# Controller_Sheet.net
KiCad netlist of a schematic drawn in Altium Designer
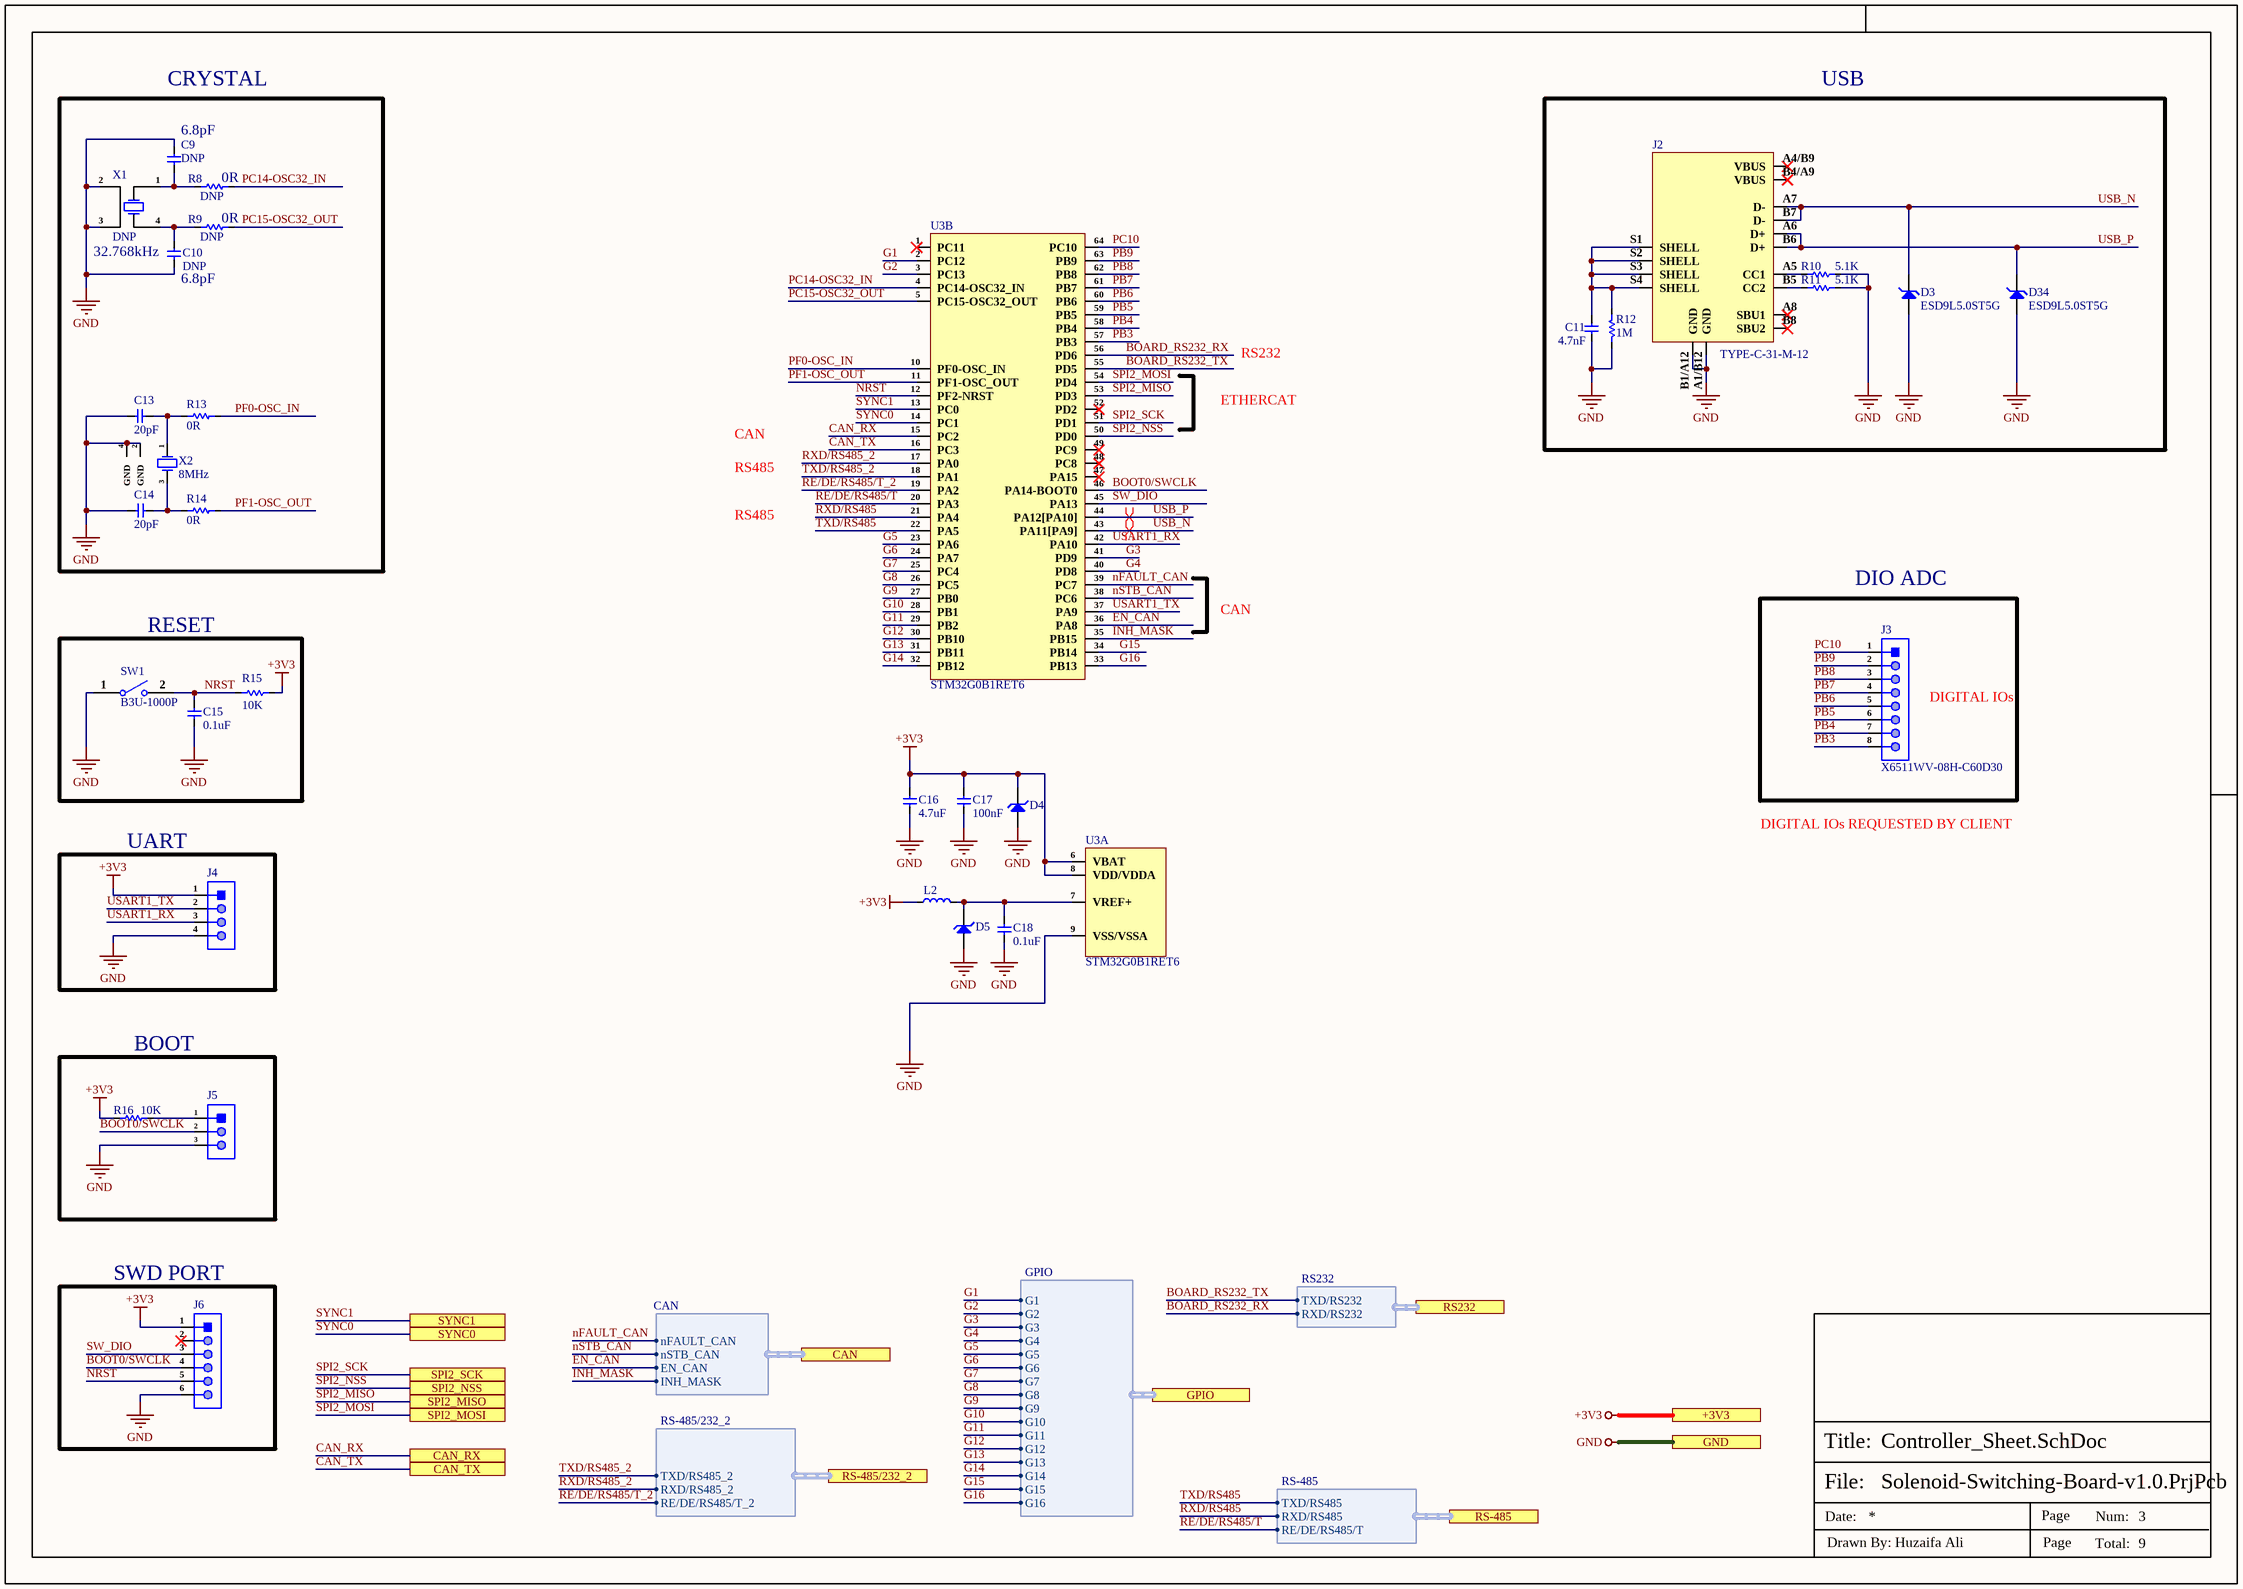
[diagram p0: Controller_Sheet.SchDoc]

(export (version "E")
  (design (tool "Eeschema 10.0.6"))
  (components
    (comp (ref "C9")
      (value "DNP")
      (footprint "Cap-0402")
      (description "CAP CER 6.8PF 50V C0G/NPO 0402")
      (fields
        (field (name "MANUFACTURER") "Yageo")
        (field (name "MANUFACTURER PART NUMBER") "CC0402CRNPO9BN6R8")
      )
      (libsource (lib "eSpark Libraries") (part "CC0402CRNPO9BN6R8"))
    )
    (comp (ref "C10")
      (value "DNP")
      (footprint "Cap-0402")
      (description "CAP CER 6.8PF 50V C0G/NPO 0402")
      (fields
        (field (name "MANUFACTURER") "Yageo")
        (field (name "MANUFACTURER PART NUMBER") "CC0402CRNPO9BN6R8")
      )
      (libsource (lib "eSpark Libraries") (part "CC0402CRNPO9BN6R8"))
    )
    (comp (ref "C11")
      (value "4.7nF")
      (footprint "Cap-0603")
      (description "CAP CER 4700PF 50V C0G/NPO 0603")
      (fields
        (field (name "MANUFACTURER") "Yageo")
        (field (name "MANUFACTURER PART NUMBER") "CC0603JRNPO9BN472")
      )
      (libsource (lib "eSpark_centralized_Library(2022)") (part "CC0603JRNPO9BN472"))
    )
    (comp (ref "C13")
      (value "20pF")
      (footprint "Cap-0402")
      (description "CAP CER 20PF 50V C0G/NPO 0402")
      (fields (field (name "LCSC PART NUMBER") "C107000") (field (name "MANUFACTURER") "Yageo"))
      (libsource (lib "eSpark Libraries") (part "CC0402JRNPO9BN200"))
    )
    (comp (ref "C14")
      (value "20pF")
      (footprint "Cap-0402")
      (description "CAP CER 20PF 50V C0G/NPO 0402")
      (fields (field (name "LCSC PART NUMBER") "C107000") (field (name "MANUFACTURER") "Yageo"))
      (libsource (lib "eSpark Libraries") (part "CC0402JRNPO9BN200"))
    )
    (comp (ref "C15")
      (value "0.1uF")
      (footprint "Cap-0402")
      (description "CAP CER 0.1UF 16V X7R 0402")
      (fields
        (field (name "MANUFACTURER") "Yageo")
        (field (name "MANUFACTURER PART NUMBER") "CC0402JRX7R7BB104")
      )
      (libsource (lib "eSpark Libraries") (part "CC0402JRX7R7BB104"))
    )
    (comp (ref "C16")
      (value "4.7uF")
      (footprint "Cap-0402")
      (description "CAP CER 4.7UF 10V X5R 0402")
      (fields
        (field (name "MANUFACTURER") "Yageo")
        (field (name "MANUFACTURER PART NUMBER") "CC0402KRX5R6BB475")
      )
      (libsource (lib "eSpark Libraries") (part "CC0402KRX5R6BB475"))
    )
    (comp (ref "C17")
      (value "100nF")
      (footprint "cap-0402")
      (description "CAP CER 0.1UF 50V X7R 0402")
      (fields
        (field (name "MANUFACTURER") "TDK")
        (field (name "MANUFACTURER PART NUMBER") "C1005X7R1H104KT000F")
      )
      (libsource (lib "eSpark Libraries") (part "C1005X7R1H104KT000F"))
    )
    (comp (ref "C18")
      (value "0.1uF")
      (footprint "Cap-0402")
      (description "CAP CER 0.1UF 16V X7R 0402")
      (fields
        (field (name "MANUFACTURER") "Yageo")
        (field (name "MANUFACTURER PART NUMBER") "CC0402JRX7R7BB104")
      )
      (libsource (lib "eSpark Libraries") (part "CC0402JRX7R7BB104"))
    )
    (comp (ref "D3")
      (value "ESD9L5.0ST5G")
      (footprint "SOD-923.")
      (description "TVS DIODE 5V 9.8V SOD923")
      (fields (field (name "MANUFACTURER") "ON Semiconductor") (field (name "LCSC PART NUMBER") "C82326"))
      (libsource (lib "eSpark Libraries") (part "ESD9L5.0ST5G"))
    )
    (comp (ref "D4")
      (value "AZ3003-01G")
      (footprint "SOD-123")
      (description "TVS SURGE PROTECTOR 1-CH 3.3V")
      (fields (field (name "MANUFACTURER") "Amazing"))
      (libsource (lib "eSpark Libraries") (part "AZ3003-01G"))
    )
    (comp (ref "D5")
      (value "AZ3003-01G")
      (footprint "SOD-123")
      (description "TVS SURGE PROTECTOR 1-CH 3.3V")
      (fields (field (name "MANUFACTURER") "Amazing"))
      (libsource (lib "eSpark Libraries") (part "AZ3003-01G"))
    )
    (comp (ref "D34")
      (value "ESD9L5.0ST5G")
      (footprint "SOD-923.")
      (description "TVS DIODE 5V 9.8V SOD923")
      (fields (field (name "MANUFACTURER") "ON Semiconductor") (field (name "LCSC PART NUMBER") "C82326"))
      (libsource (lib "eSpark Libraries") (part "ESD9L5.0ST5G"))
    )
    (comp (ref "J2")
      (value "TYPE-C-31-M-12")
      (footprint "TYPE-C-31-M-12_")
      (description "5A 1 16P Female Type-C SMD USB Connectors ROHS")
      (fields
        (field (name "MANUFACTURER") "Korean Hroparts Elec")
        (field (name "LCSC PART NUMBER") "C165948")
      )
      (libsource (lib "eSpark Libraries") (part "TYPE-C-31-M-12"))
    )
    (comp (ref "J3")
      (value "X6511WV-08H-C60D30")
      (footprint "HDR 1x8 TH male")
      (fields (field (name "MANUFACTURER") "XKB") (field (name "LCSC PART NUMBER") "C706880"))
      (libsource (lib "eSpark Libraries") (part "X6511WV-08H-C60D30"))
    )
    (comp (ref "J4")
      (value "X6511WV-04H-C60D30")
      (footprint "HDR1X4_")
      (fields (field (name "MANUFACTURER") "XKB") (field (name "LCSC PART NUMBER") "C706876"))
      (libsource (lib "eSpark Libraries") (part "X6511WV-04H-C60D30"))
    )
    (comp (ref "J5")
      (value "68000-103HLF")
      (footprint "HDR1X3_")
      (description "CONN HEADER VERT 3POS 2.54MM")
      (fields (field (name "LCSC PART NUMBER") "C168677"))
      (libsource (lib "eSpark Libraries") (part "68000-103HLF"))
    )
    (comp (ref "J6")
      (value "X6511WV-06H-C60D30")
      (footprint "HDR1X6_")
      (fields (field (name "MANUFACTURER") "XKB") (field (name "LCSC PART NUMBER") "C706878"))
      (libsource (lib "eSpark Libraries") (part "X6511WV-06H-C60D30"))
    )
    (comp (ref "L2")
      (value "BLM15AG601SN1D")
      (footprint "IND-0402")
      (description "FERRITE BEAD 600 OHM 0402 1LN")
      (fields (field (name "MANUFACTURER") "Murata") (field (name "TOLERANCE") "25%"))
      (libsource (lib "eSpark Libraries") (part "BLM15AG601SN1D"))
    )
    (comp (ref "R8")
      (value "DNP")
      (footprint "Res-0603")
      (description "RES 0 OHM JUMPER 1/10W 0603")
      (fields
        (field (name "MANUFACTURER") "Yageo")
        (field (name "MANUFACTURER PART NUMBER") "RC0603JR-070RL")
      )
      (libsource (lib "eSpark Libraries") (part "RC0603JR-070RL"))
    )
    (comp (ref "R9")
      (value "DNP")
      (footprint "Res-0603")
      (description "RES 0 OHM JUMPER 1/10W 0603")
      (fields
        (field (name "MANUFACTURER") "Yageo")
        (field (name "MANUFACTURER PART NUMBER") "RC0603JR-070RL")
      )
      (libsource (lib "eSpark Libraries") (part "RC0603JR-070RL"))
    )
    (comp (ref "R10")
      (value "5.1K")
      (footprint "Res-0402")
      (description "RES 5.1K OHM 1% 1/16W 0402")
      (fields
        (field (name "MANUFACTURER") "Yageo")
        (field (name "MANUFACTURER PART NUMBER") "RC0402FR-075K1L")
      )
      (libsource (lib "eSpark Libraries") (part "RC0402FR-075K1L"))
    )
    (comp (ref "R11")
      (value "5.1K")
      (footprint "Res-0402")
      (description "RES 5.1K OHM 1% 1/16W 0402")
      (fields
        (field (name "MANUFACTURER") "Yageo")
        (field (name "MANUFACTURER PART NUMBER") "RC0402FR-075K1L")
      )
      (libsource (lib "eSpark Libraries") (part "RC0402FR-075K1L"))
    )
    (comp (ref "R12")
      (value "1M")
      (footprint "Res-0402")
      (description "RES SMD 1M OHM 5% 1/16W 0402")
      (fields
        (field (name "MANUFACTURER") "Yageo")
        (field (name "MANUFACTURER PART NUMBER") "AF0402JR-071ML")
      )
      (libsource (lib "eSpark_centralized_Library(2022)") (part "AF0402JR-071ML"))
    )
    (comp (ref "R13")
      (value "0R")
      (footprint "Res-0603")
      (description "RES 0 OHM JUMPER 1/10W 0603")
      (fields
        (field (name "MANUFACTURER") "Yageo")
        (field (name "MANUFACTURER PART NUMBER") "RC0603JR-070RL")
      )
      (libsource (lib "eSpark Libraries") (part "RC0603JR-070RL"))
    )
    (comp (ref "R14")
      (value "0R")
      (footprint "Res-0603")
      (description "RES 0 OHM JUMPER 1/10W 0603")
      (fields
        (field (name "MANUFACTURER") "Yageo")
        (field (name "MANUFACTURER PART NUMBER") "RC0603JR-070RL")
      )
      (libsource (lib "eSpark Libraries") (part "RC0603JR-070RL"))
    )
    (comp (ref "R15")
      (value "10K")
      (footprint "Res-0402")
      (description "RES 10K OHM 1% 1/16W 0402")
      (fields
        (field (name "MANUFACTURER") "Yageo")
        (field (name "MANUFACTURER PART NUMBER") "RC0402FR-0710KL")
      )
      (libsource (lib "eSpark Libraries") (part "RC0402FR-0710KL"))
    )
    (comp (ref "R16")
      (value "10K")
      (footprint "Res-0402")
      (description "RES 10K OHM 1% 1/16W 0402")
      (fields
        (field (name "MANUFACTURER") "Yageo")
        (field (name "MANUFACTURER PART NUMBER") "RC0402FR-0710KL")
      )
      (libsource (lib "eSpark Libraries") (part "RC0402FR-0710KL"))
    )
    (comp (ref "SW1")
      (value "B3U-1000P")
      (footprint "B3U-1000P")
      (description "SWITCH TACTILE SPST-NO 0.05A 12V")
      (fields (field (name "MANUFACTURER") "Omron") (field (name "LCSC PART NUMBER") "C231329"))
      (libsource (lib "eSpark Libraries") (part "B3U-1000P"))
    )
    (comp (ref "U3")
      (value "STM32G0B1RET6")
      (footprint "LQFP-64(10x10)")
      (description "IC MCU 32BIT 512KB FLASH 64LQFP")
      (fields (field (name "MANUFACTURER") "STMicroelectronics") (field (name "LCSC PART NUMBER") "C2829307"))
      (libsource (lib "eSpark Libraries") (part "STM32G0B1RET6"))
    )
    (comp (ref "X1")
      (value "DNP")
      (footprint "MC-306")
      (description "32.768kHz 12.5pF ±20ppm MC-306 Crystals ROHS")
      (fields
        (field (name "MANUFACTURER") "Seiko Epson")
        (field (name "MANUFACTURER PART NUMBER") "MC-306 32.7680K-A0:ROHS")
      )
      (libsource (lib "eSpark Libraries") (part "MC-306 32.7680K-A0{colon}ROHS"))
    )
    (comp (ref "X2")
      (value "8MHz")
      (footprint "5TJ480000XYLBC_")
      (description "8MHz 18pF ±10ppm SMD5032-4P Crystals ROHS")
      (fields (field (name "MANUFACTURER") "JYJE") (field (name "MANUFACTURER PART NUMBER") "5TJ480000XYLBC"))
      (libsource (lib "eSpark Libraries") (part "5TJ480000XYLBC"))
    )
  )
  (nets
    (net (code "6") (name "+3V3") (class "Default")
      (node (ref "C16") (pin "2") (pinfunction "2_2") (pintype "passive"))
      (node (ref "C17") (pin "2") (pinfunction "2_2") (pintype "passive"))
      (node (ref "D4") (pin "2") (pinfunction "K_2") (pintype "passive"))
      (node (ref "J4") (pin "1") (pinfunction "1_1") (pintype "passive"))
      (node (ref "J6") (pin "1") (pinfunction "1_1") (pintype "passive"))
      (node (ref "L2") (pin "1") (pinfunction "1_1") (pintype "passive"))
      (node (ref "R15") (pin "2") (pinfunction "2_2") (pintype "passive"))
      (node (ref "R16") (pin "2") (pinfunction "2_2") (pintype "passive"))
      (node (ref "U3") (pin "6") (pinfunction "VBAT_6") (pintype "passive"))
      (node (ref "U3") (pin "8") (pinfunction "VDD/VDDA_8") (pintype "passive"))
    )
    (net (code "7") (name "/BOARD_RS232_RX") (class "Default")
      (node (ref "U3") (pin "56") (pinfunction "PD6_56") (pintype "passive"))
    )
    (net (code "8") (name "/BOARD_RS232_TX") (class "Default")
      (node (ref "U3") (pin "55") (pinfunction "PD5_55") (pintype "passive"))
    )
    (net (code "9") (name "/BOOT0{slash}SWCLK") (class "Default")
      (node (ref "J5") (pin "2") (pinfunction "2_2") (pintype "passive"))
      (node (ref "J6") (pin "4") (pinfunction "4_4") (pintype "passive"))
      (node (ref "U3") (pin "46") (pinfunction "PA14-BOOT0_46") (pintype "passive"))
    )
    (net (code "10") (name "/CAN_RX") (class "Default")
      (node (ref "U3") (pin "15") (pinfunction "PC2_15") (pintype "passive"))
    )
    (net (code "11") (name "/CAN_TX") (class "Default")
      (node (ref "U3") (pin "16") (pinfunction "PC3_16") (pintype "passive"))
    )
    (net (code "12") (name "/EN_CAN") (class "Default")
      (node (ref "U3") (pin "36") (pinfunction "PA8_36") (pintype "passive"))
    )
    (net (code "13") (name "/G1") (class "Default")
      (node (ref "U3") (pin "2") (pinfunction "PC12_2") (pintype "passive"))
    )
    (net (code "14") (name "/G2") (class "Default")
      (node (ref "U3") (pin "3") (pinfunction "PC13_3") (pintype "passive"))
    )
    (net (code "15") (name "/G3") (class "Default")
      (node (ref "U3") (pin "41") (pinfunction "PD9_41") (pintype "passive"))
    )
    (net (code "16") (name "/G4") (class "Default")
      (node (ref "U3") (pin "40") (pinfunction "PD8_40") (pintype "passive"))
    )
    (net (code "17") (name "/G5") (class "Default")
      (node (ref "U3") (pin "23") (pinfunction "PA6_23") (pintype "passive"))
    )
    (net (code "18") (name "/G6") (class "Default")
      (node (ref "U3") (pin "24") (pinfunction "PA7_24") (pintype "passive"))
    )
    (net (code "19") (name "/G7") (class "Default")
      (node (ref "U3") (pin "25") (pinfunction "PC4_25") (pintype "passive"))
    )
    (net (code "20") (name "/G8") (class "Default")
      (node (ref "U3") (pin "26") (pinfunction "PC5_26") (pintype "passive"))
    )
    (net (code "21") (name "/G9") (class "Default")
      (node (ref "U3") (pin "27") (pinfunction "PB0_27") (pintype "passive"))
    )
    (net (code "22") (name "/G10") (class "Default")
      (node (ref "U3") (pin "28") (pinfunction "PB1_28") (pintype "passive"))
    )
    (net (code "23") (name "/G11") (class "Default")
      (node (ref "U3") (pin "29") (pinfunction "PB2_29") (pintype "passive"))
    )
    (net (code "24") (name "/G12") (class "Default")
      (node (ref "U3") (pin "30") (pinfunction "PB10_30") (pintype "passive"))
    )
    (net (code "25") (name "/G13") (class "Default")
      (node (ref "U3") (pin "31") (pinfunction "PB11_31") (pintype "passive"))
    )
    (net (code "26") (name "/G14") (class "Default")
      (node (ref "U3") (pin "32") (pinfunction "PB12_32") (pintype "passive"))
    )
    (net (code "27") (name "/G15") (class "Default")
      (node (ref "U3") (pin "34") (pinfunction "PB14_34") (pintype "passive"))
    )
    (net (code "28") (name "/G16") (class "Default")
      (node (ref "U3") (pin "33") (pinfunction "PB13_33") (pintype "passive"))
    )
    (net (code "29") (name "/INH_MASK") (class "Default")
      (node (ref "U3") (pin "35") (pinfunction "PB15_35") (pintype "passive"))
    )
    (net (code "30") (name "/NRST") (class "Default")
      (node (ref "C15") (pin "2") (pinfunction "2_2") (pintype "passive"))
      (node (ref "J6") (pin "5") (pinfunction "5_5") (pintype "passive"))
      (node (ref "R15") (pin "1") (pinfunction "1_1") (pintype "passive"))
      (node (ref "SW1") (pin "2") (pinfunction "2_2") (pintype "passive"))
      (node (ref "U3") (pin "12") (pinfunction "PF2-NRST_12") (pintype "passive"))
    )
    (net (code "31") (name "/PB3") (class "Default")
      (node (ref "J3") (pin "8") (pinfunction "8_8") (pintype "passive"))
      (node (ref "U3") (pin "57") (pinfunction "PB3_57") (pintype "passive"))
    )
    (net (code "32") (name "/PB4") (class "Default")
      (node (ref "J3") (pin "7") (pinfunction "7_7") (pintype "passive"))
      (node (ref "U3") (pin "58") (pinfunction "PB4_58") (pintype "passive"))
    )
    (net (code "33") (name "/PB5") (class "Default")
      (node (ref "J3") (pin "6") (pinfunction "6_6") (pintype "passive"))
      (node (ref "U3") (pin "59") (pinfunction "PB5_59") (pintype "passive"))
    )
    (net (code "34") (name "/PB6") (class "Default")
      (node (ref "J3") (pin "5") (pinfunction "5_5") (pintype "passive"))
      (node (ref "U3") (pin "60") (pinfunction "PB6_60") (pintype "passive"))
    )
    (net (code "35") (name "/PB7") (class "Default")
      (node (ref "J3") (pin "4") (pinfunction "4_4") (pintype "passive"))
      (node (ref "U3") (pin "61") (pinfunction "PB7_61") (pintype "passive"))
    )
    (net (code "36") (name "/PB8") (class "Default")
      (node (ref "J3") (pin "3") (pinfunction "3_3") (pintype "passive"))
      (node (ref "U3") (pin "62") (pinfunction "PB8_62") (pintype "passive"))
    )
    (net (code "37") (name "/PB9") (class "Default")
      (node (ref "J3") (pin "2") (pinfunction "2_2") (pintype "passive"))
      (node (ref "U3") (pin "63") (pinfunction "PB9_63") (pintype "passive"))
    )
    (net (code "38") (name "/PC10") (class "Default")
      (node (ref "J3") (pin "1") (pinfunction "1_1") (pintype "passive"))
      (node (ref "U3") (pin "64") (pinfunction "PC10_64") (pintype "passive"))
    )
    (net (code "39") (name "/PC14-OSC32_IN") (class "Default")
      (node (ref "R8") (pin "2") (pinfunction "2_2") (pintype "passive"))
      (node (ref "U3") (pin "4") (pinfunction "PC14-OSC32_IN_4") (pintype "passive"))
    )
    (net (code "40") (name "/PC15-OSC32_OUT") (class "Default")
      (node (ref "R9") (pin "2") (pinfunction "2_2") (pintype "passive"))
      (node (ref "U3") (pin "5") (pinfunction "PC15-OSC32_OUT_5") (pintype "passive"))
    )
    (net (code "41") (name "/PF0-OSC_IN") (class "Default")
      (node (ref "R13") (pin "2") (pinfunction "2_2") (pintype "passive"))
      (node (ref "U3") (pin "10") (pinfunction "PF0-OSC_IN_10") (pintype "passive"))
    )
    (net (code "42") (name "/PF1-OSC_OUT") (class "Default")
      (node (ref "R14") (pin "2") (pinfunction "2_2") (pintype "passive"))
      (node (ref "U3") (pin "11") (pinfunction "PF1-OSC_OUT_11") (pintype "passive"))
    )
    (net (code "43") (name "/RE{slash}DE{slash}RS485{slash}T") (class "Default")
      (node (ref "U3") (pin "20") (pinfunction "PA3_20") (pintype "passive"))
    )
    (net (code "44") (name "/RE{slash}DE{slash}RS485{slash}T_2") (class "Default")
      (node (ref "U3") (pin "19") (pinfunction "PA2_19") (pintype "passive"))
    )
    (net (code "45") (name "/RXD{slash}RS485") (class "Default")
      (node (ref "U3") (pin "21") (pinfunction "PA4_21") (pintype "passive"))
    )
    (net (code "46") (name "/RXD{slash}RS485_2") (class "Default")
      (node (ref "U3") (pin "17") (pinfunction "PA0_17") (pintype "passive"))
    )
    (net (code "47") (name "/SPI2_MISO") (class "Default")
      (node (ref "U3") (pin "53") (pinfunction "PD3_53") (pintype "passive"))
    )
    (net (code "48") (name "/SPI2_MOSI") (class "Default")
      (node (ref "U3") (pin "54") (pinfunction "PD4_54") (pintype "passive"))
    )
    (net (code "49") (name "/SPI2_NSS") (class "Default")
      (node (ref "U3") (pin "50") (pinfunction "PD0_50") (pintype "passive"))
    )
    (net (code "50") (name "/SPI2_SCK") (class "Default")
      (node (ref "U3") (pin "51") (pinfunction "PD1_51") (pintype "passive"))
    )
    (net (code "51") (name "/SW_DIO") (class "Default")
      (node (ref "J6") (pin "3") (pinfunction "3_3") (pintype "passive"))
      (node (ref "U3") (pin "45") (pinfunction "PA13_45") (pintype "passive"))
    )
    (net (code "52") (name "/SYNC0") (class "Default")
      (node (ref "U3") (pin "14") (pinfunction "PC1_14") (pintype "passive"))
    )
    (net (code "53") (name "/SYNC1") (class "Default")
      (node (ref "U3") (pin "13") (pinfunction "PC0_13") (pintype "passive"))
    )
    (net (code "54") (name "/TXD{slash}RS485") (class "Default")
      (node (ref "U3") (pin "22") (pinfunction "PA5_22") (pintype "passive"))
    )
    (net (code "55") (name "/TXD{slash}RS485_2") (class "Default")
      (node (ref "U3") (pin "18") (pinfunction "PA1_18") (pintype "passive"))
    )
    (net (code "56") (name "/USART1_RX") (class "Default")
      (node (ref "J4") (pin "3") (pinfunction "3_3") (pintype "passive"))
      (node (ref "U3") (pin "42") (pinfunction "PA10_42") (pintype "passive"))
    )
    (net (code "57") (name "/USART1_TX") (class "Default")
      (node (ref "J4") (pin "2") (pinfunction "2_2") (pintype "passive"))
      (node (ref "U3") (pin "37") (pinfunction "PA9_37") (pintype "passive"))
    )
    (net (code "58") (name "/USB_N") (class "Default")
      (node (ref "D3") (pin "1") (pinfunction "K_1") (pintype "passive"))
      (node (ref "J2") (pin "A7") (pinfunction "D-_A7") (pintype "passive"))
      (node (ref "J2") (pin "B7") (pinfunction "D-_B7") (pintype "passive"))
      (node (ref "U3") (pin "43") (pinfunction "PA11[PA9]_43") (pintype "passive"))
    )
    (net (code "59") (name "/USB_P") (class "Default")
      (node (ref "D34") (pin "1") (pinfunction "K_1") (pintype "passive"))
      (node (ref "J2") (pin "A6") (pinfunction "D+_A6") (pintype "passive"))
      (node (ref "J2") (pin "B6") (pinfunction "D+_B6") (pintype "passive"))
      (node (ref "U3") (pin "44") (pinfunction "PA12[PA10]_44") (pintype "passive"))
    )
    (net (code "60") (name "/nFAULT_CAN") (class "Default")
      (node (ref "U3") (pin "39") (pinfunction "PC7_39") (pintype "passive"))
    )
    (net (code "61") (name "/nSTB_CAN") (class "Default")
      (node (ref "U3") (pin "38") (pinfunction "PC6_38") (pintype "passive"))
    )
    (net (code "67") (name "GND") (class "Default")
      (node (ref "C10") (pin "2") (pinfunction "2_2") (pintype "passive"))
      (node (ref "C11") (pin "1") (pinfunction "1_1") (pintype "passive"))
      (node (ref "C13") (pin "1") (pinfunction "1_1") (pintype "passive"))
      (node (ref "C14") (pin "2") (pinfunction "2_2") (pintype "passive"))
      (node (ref "C15") (pin "1") (pinfunction "1_1") (pintype "passive"))
      (node (ref "C16") (pin "1") (pinfunction "1_1") (pintype "passive"))
      (node (ref "C17") (pin "1") (pinfunction "1_1") (pintype "passive"))
      (node (ref "C18") (pin "1") (pinfunction "1_1") (pintype "passive"))
      (node (ref "C9") (pin "1") (pinfunction "1_1") (pintype "passive"))
      (node (ref "D3") (pin "2") (pinfunction "A_2") (pintype "passive"))
      (node (ref "D34") (pin "2") (pinfunction "A_2") (pintype "passive"))
      (node (ref "D4") (pin "1") (pinfunction "A_1") (pintype "passive"))
      (node (ref "D5") (pin "1") (pinfunction "A_1") (pintype "passive"))
      (node (ref "J2") (pin "A1/B12") (pinfunction "GND_A1/B12") (pintype "power_in"))
      (node (ref "J2") (pin "B1/A12") (pinfunction "GND_B1/A12") (pintype "power_in"))
      (node (ref "J4") (pin "4") (pinfunction "4_4") (pintype "passive"))
      (node (ref "J5") (pin "3") (pinfunction "3_3") (pintype "passive"))
      (node (ref "J6") (pin "6") (pinfunction "6_6") (pintype "passive"))
      (node (ref "R10") (pin "2") (pinfunction "2_2") (pintype "passive"))
      (node (ref "R11") (pin "2") (pinfunction "2_2") (pintype "passive"))
      (node (ref "R12") (pin "2") (pinfunction "2_2") (pintype "passive"))
      (node (ref "SW1") (pin "1") (pinfunction "1_1") (pintype "passive"))
      (node (ref "U3") (pin "9") (pinfunction "VSS/VSSA_9") (pintype "passive"))
      (node (ref "X1") (pin "2") (pinfunction "2_2") (pintype "passive"))
      (node (ref "X1") (pin "3") (pinfunction "3_3") (pintype "passive"))
      (node (ref "X2") (pin "2") (pinfunction "GND_2") (pintype "passive"))
      (node (ref "X2") (pin "4") (pinfunction "GND_4") (pintype "passive"))
    )
    (net (code "68") (name "Net-(C11-Pad2)") (class "Default")
      (node (ref "C11") (pin "2") (pinfunction "2_2") (pintype "passive"))
      (node (ref "J2") (pin "S1") (pinfunction "SHELL_S1") (pintype "passive"))
      (node (ref "J2") (pin "S2") (pinfunction "SHELL_S2") (pintype "passive"))
      (node (ref "J2") (pin "S3") (pinfunction "SHELL_S3") (pintype "passive"))
      (node (ref "J2") (pin "S4") (pinfunction "SHELL_S4") (pintype "passive"))
      (node (ref "R12") (pin "1") (pinfunction "1_1") (pintype "passive"))
    )
    (net (code "69") (name "Net-(D5-K)") (class "Default")
      (node (ref "C18") (pin "2") (pinfunction "2_2") (pintype "passive"))
      (node (ref "D5") (pin "2") (pinfunction "K_2") (pintype "passive"))
      (node (ref "L2") (pin "2") (pinfunction "2_2") (pintype "passive"))
      (node (ref "U3") (pin "7") (pinfunction "VREF+_7") (pintype "passive"))
    )
    (net (code "70") (name "Net-(J2-CC1)") (class "Default")
      (node (ref "J2") (pin "A5") (pinfunction "CC1_A5") (pintype "passive"))
      (node (ref "R10") (pin "1") (pinfunction "1_1") (pintype "passive"))
    )
    (net (code "71") (name "Net-(J2-CC2)") (class "Default")
      (node (ref "J2") (pin "B5") (pinfunction "CC2_B5") (pintype "passive"))
      (node (ref "R11") (pin "1") (pinfunction "1_1") (pintype "passive"))
    )
    (net (code "72") (name "Net-(J5-Pad1)") (class "Default")
      (node (ref "J5") (pin "1") (pinfunction "1_1") (pintype "passive"))
      (node (ref "R16") (pin "1") (pinfunction "1_1") (pintype "passive"))
    )
    (net (code "73") (name "Net-(X1-OSC1)") (class "Default")
      (node (ref "C9") (pin "2") (pinfunction "2_2") (pintype "passive"))
      (node (ref "R8") (pin "1") (pinfunction "1_1") (pintype "passive"))
      (node (ref "X1") (pin "1") (pinfunction "OSC1_1") (pintype "passive"))
    )
    (net (code "74") (name "Net-(X1-OSC2)") (class "Default")
      (node (ref "C10") (pin "1") (pinfunction "1_1") (pintype "passive"))
      (node (ref "R9") (pin "1") (pinfunction "1_1") (pintype "passive"))
      (node (ref "X1") (pin "4") (pinfunction "OSC2_4") (pintype "passive"))
    )
    (net (code "75") (name "Net-(X2-OSC1)") (class "Default")
      (node (ref "C13") (pin "2") (pinfunction "2_2") (pintype "passive"))
      (node (ref "R13") (pin "1") (pinfunction "1_1") (pintype "passive"))
      (node (ref "X2") (pin "1") (pinfunction "OSC1_1") (pintype "passive"))
    )
    (net (code "76") (name "Net-(X2-OSC2)") (class "Default")
      (node (ref "C14") (pin "1") (pinfunction "1_1") (pintype "passive"))
      (node (ref "R14") (pin "1") (pinfunction "1_1") (pintype "passive"))
      (node (ref "X2") (pin "3") (pinfunction "OSC2_3") (pintype "passive"))
    )
    (net (code "77") (name "unconnected-(J2-SBU1-PadA8)") (class "Default")
      (node (ref "J2") (pin "A8") (pinfunction "SBU1_A8") (pintype "passive+no_connect"))
    )
    (net (code "78") (name "unconnected-(J2-SBU2-PadB8)") (class "Default")
      (node (ref "J2") (pin "B8") (pinfunction "SBU2_B8") (pintype "passive+no_connect"))
    )
    (net (code "79") (name "unconnected-(J2-VBUS-PadA4{slash}B9)") (class "Default")
      (node (ref "J2") (pin "A4/B9") (pinfunction "VBUS_A4/B9") (pintype "power_in+no_connect"))
    )
    (net (code "80") (name "unconnected-(J2-VBUS-PadB4{slash}A9)") (class "Default")
      (node (ref "J2") (pin "B4/A9") (pinfunction "VBUS_B4/A9") (pintype "power_in+no_connect"))
    )
    (net (code "81") (name "unconnected-(J6-Pad2)") (class "Default")
      (node (ref "J6") (pin "2") (pinfunction "2_2") (pintype "passive+no_connect"))
    )
    (net (code "82") (name "unconnected-(U3B-PA15-Pad47)") (class "Default")
      (node (ref "U3") (pin "47") (pinfunction "PA15_47") (pintype "passive+no_connect"))
    )
    (net (code "83") (name "unconnected-(U3B-PC8-Pad48)") (class "Default")
      (node (ref "U3") (pin "48") (pinfunction "PC8_48") (pintype "passive+no_connect"))
    )
    (net (code "84") (name "unconnected-(U3B-PC9-Pad49)") (class "Default")
      (node (ref "U3") (pin "49") (pinfunction "PC9_49") (pintype "passive+no_connect"))
    )
    (net (code "85") (name "unconnected-(U3B-PC11-Pad1)") (class "Default")
      (node (ref "U3") (pin "1") (pinfunction "PC11_1") (pintype "passive+no_connect"))
    )
    (net (code "86") (name "unconnected-(U3B-PD2-Pad52)") (class "Default")
      (node (ref "U3") (pin "52") (pinfunction "PD2_52") (pintype "passive+no_connect"))
    )
  )
)
